# design.net
KiCad netlist of a schematic drawn in Altium Designer
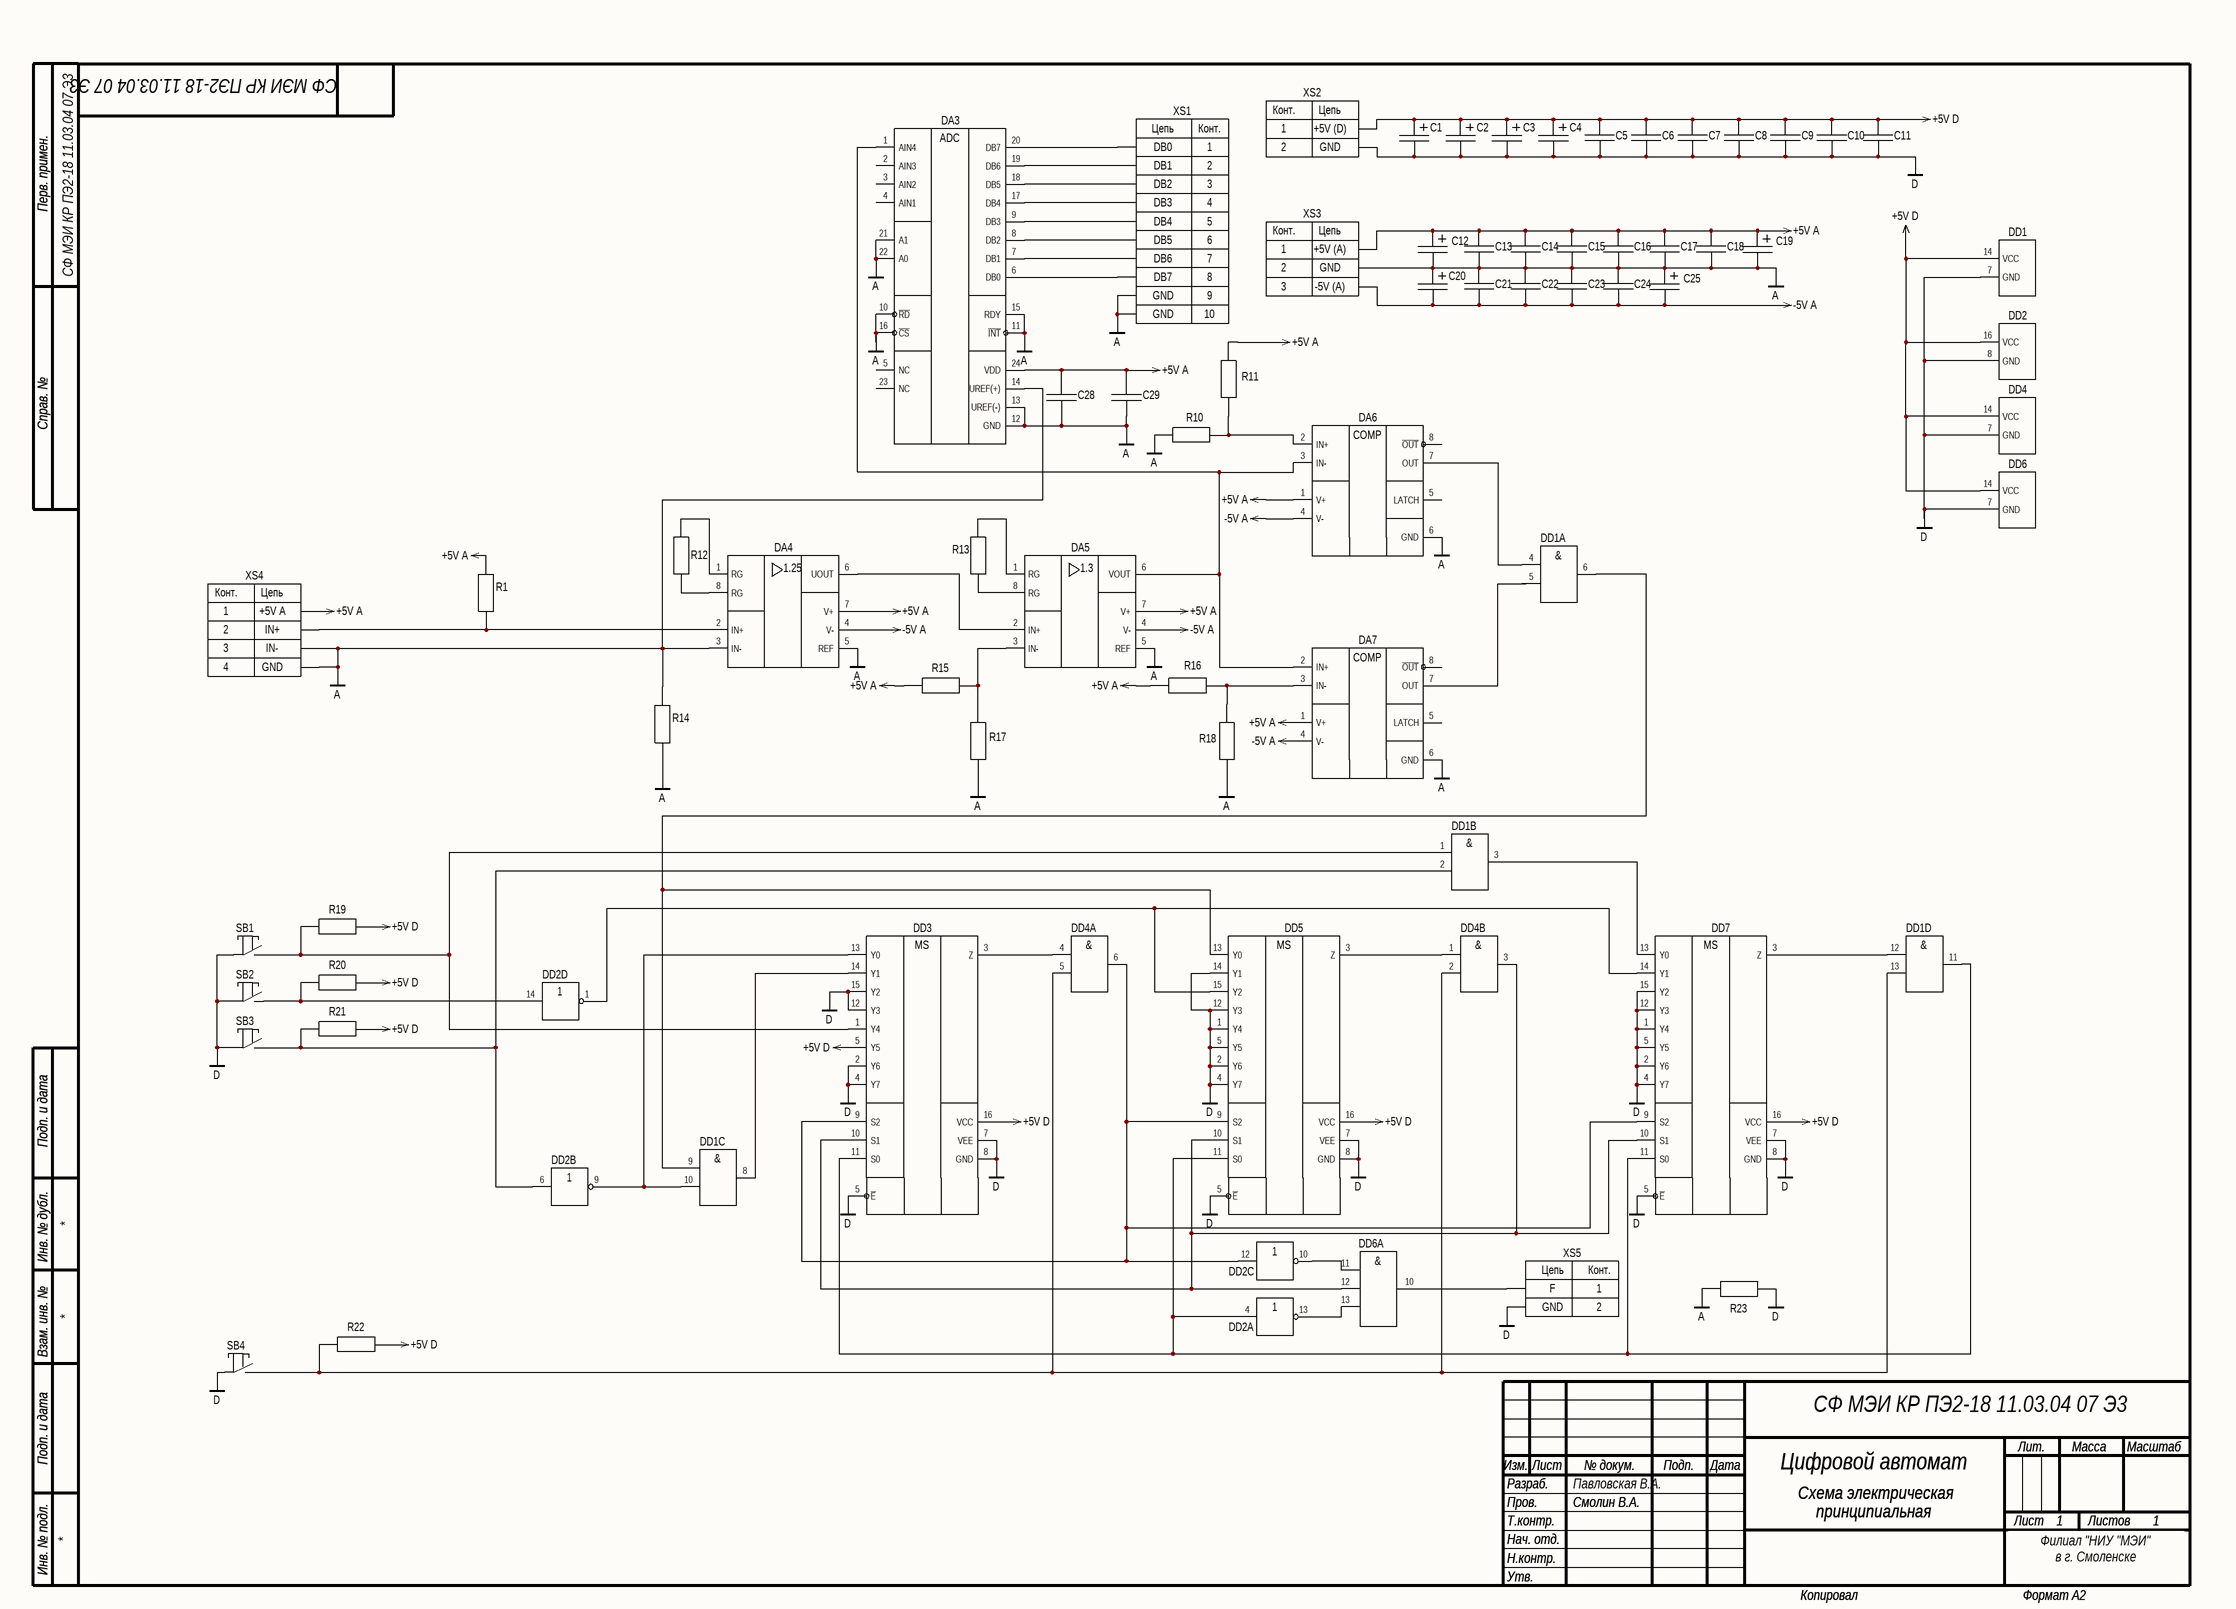
[diagram p0: Схема принципиальнаяСаня.SchDoc]

(export (version "E")
  (design (tool "Eeschema 10.0.6"))
  (components
    (comp (ref "C5")
      (value "0.1uF")
      (footprint "Кер.ЧИП конд. 0.1 мкФ X7R 50В 10% 0805")
      (description "Кер.ЧИП конд. 0.1 мкФ X7R 50В 10% 0805")
      (libsource (lib "УГО") (part "Кер.ЧИП конд. 0.1 мкФ X7R 50В 10% 0805"))
    )
    (comp (ref "C6")
      (value "0.1uF")
      (footprint "Кер.ЧИП конд. 0.1 мкФ X7R 50В 10% 0805")
      (description "Кер.ЧИП конд. 0.1 мкФ X7R 50В 10% 0805")
      (libsource (lib "УГО") (part "Кер.ЧИП конд. 0.1 мкФ X7R 50В 10% 0805"))
    )
    (comp (ref "C7")
      (value "0.1uF")
      (footprint "Кер.ЧИП конд. 0.1 мкФ X7R 50В 10% 0805")
      (description "Кер.ЧИП конд. 0.1 мкФ X7R 50В 10% 0805")
      (libsource (lib "УГО") (part "Кер.ЧИП конд. 0.1 мкФ X7R 50В 10% 0805"))
    )
    (comp (ref "C8")
      (value "0.1uF")
      (footprint "Кер.ЧИП конд. 0.1 мкФ X7R 50В 10% 0805")
      (description "Кер.ЧИП конд. 0.1 мкФ X7R 50В 10% 0805")
      (libsource (lib "УГО") (part "Кер.ЧИП конд. 0.1 мкФ X7R 50В 10% 0805"))
    )
    (comp (ref "C9")
      (value "0.1uF")
      (footprint "Кер.ЧИП конд. 0.1 мкФ X7R 50В 10% 0805")
      (description "Кер.ЧИП конд. 0.1 мкФ X7R 50В 10% 0805")
      (libsource (lib "УГО") (part "Кер.ЧИП конд. 0.1 мкФ X7R 50В 10% 0805"))
    )
    (comp (ref "C10")
      (value "0.1uF")
      (footprint "Кер.ЧИП конд. 0.1 мкФ X7R 50В 10% 0805")
      (description "Кер.ЧИП конд. 0.1 мкФ X7R 50В 10% 0805")
      (libsource (lib "УГО") (part "Кер.ЧИП конд. 0.1 мкФ X7R 50В 10% 0805"))
    )
    (comp (ref "C11")
      (value "0.1uF")
      (footprint "Кер.ЧИП конд. 0.1 мкФ X7R 50В 10% 0805")
      (description "Кер.ЧИП конд. 0.1 мкФ X7R 50В 10% 0805")
      (libsource (lib "УГО") (part "Кер.ЧИП конд. 0.1 мкФ X7R 50В 10% 0805"))
    )
    (comp (ref "C13")
      (value "0.1uF")
      (footprint "Кер.ЧИП конд. 0.1 мкФ X7R 50В 10% 0805")
      (description "Кер.ЧИП конд. 0.1 мкФ X7R 50В 10% 0805")
      (libsource (lib "УГО") (part "Кер.ЧИП конд. 0.1 мкФ X7R 50В 10% 0805"))
    )
    (comp (ref "C14")
      (value "0.1uF")
      (footprint "Кер.ЧИП конд. 0.1 мкФ X7R 50В 10% 0805")
      (description "Кер.ЧИП конд. 0.1 мкФ X7R 50В 10% 0805")
      (libsource (lib "УГО") (part "Кер.ЧИП конд. 0.1 мкФ X7R 50В 10% 0805"))
    )
    (comp (ref "C15")
      (value "0.1uF")
      (footprint "Кер.ЧИП конд. 0.1 мкФ X7R 50В 10% 0805")
      (description "Кер.ЧИП конд. 0.1 мкФ X7R 50В 10% 0805")
      (libsource (lib "УГО") (part "Кер.ЧИП конд. 0.1 мкФ X7R 50В 10% 0805"))
    )
    (comp (ref "C16")
      (value "0.1uF")
      (footprint "Кер.ЧИП конд. 0.1 мкФ X7R 50В 10% 0805")
      (description "Кер.ЧИП конд. 0.1 мкФ X7R 50В 10% 0805")
      (libsource (lib "УГО") (part "Кер.ЧИП конд. 0.1 мкФ X7R 50В 10% 0805"))
    )
    (comp (ref "C17")
      (value "0.1uF")
      (footprint "Кер.ЧИП конд. 0.1 мкФ X7R 50В 10% 0805")
      (description "Кер.ЧИП конд. 0.1 мкФ X7R 50В 10% 0805")
      (libsource (lib "УГО") (part "Кер.ЧИП конд. 0.1 мкФ X7R 50В 10% 0805"))
    )
    (comp (ref "C18")
      (value "0.1uF")
      (footprint "Кер.ЧИП конд. 0.1 мкФ X7R 50В 10% 0805")
      (description "Кер.ЧИП конд. 0.1 мкФ X7R 50В 10% 0805")
      (libsource (lib "УГО") (part "Кер.ЧИП конд. 0.1 мкФ X7R 50В 10% 0805"))
    )
    (comp (ref "C21")
      (value "0.1uF")
      (footprint "Кер.ЧИП конд. 0.1 мкФ X7R 50В 10% 0805")
      (description "Кер.ЧИП конд. 0.1 мкФ X7R 50В 10% 0805")
      (libsource (lib "УГО") (part "Кер.ЧИП конд. 0.1 мкФ X7R 50В 10% 0805"))
    )
    (comp (ref "C22")
      (value "0.1uF")
      (footprint "Кер.ЧИП конд. 0.1 мкФ X7R 50В 10% 0805")
      (description "Кер.ЧИП конд. 0.1 мкФ X7R 50В 10% 0805")
      (libsource (lib "УГО") (part "Кер.ЧИП конд. 0.1 мкФ X7R 50В 10% 0805"))
    )
    (comp (ref "C23")
      (value "0.1uF")
      (footprint "Кер.ЧИП конд. 0.1 мкФ X7R 50В 10% 0805")
      (description "Кер.ЧИП конд. 0.1 мкФ X7R 50В 10% 0805")
      (libsource (lib "УГО") (part "Кер.ЧИП конд. 0.1 мкФ X7R 50В 10% 0805"))
    )
    (comp (ref "C24")
      (value "0.1uF")
      (footprint "Кер.ЧИП конд. 0.1 мкФ X7R 50В 10% 0805")
      (description "Кер.ЧИП конд. 0.1 мкФ X7R 50В 10% 0805")
      (libsource (lib "УГО") (part "Кер.ЧИП конд. 0.1 мкФ X7R 50В 10% 0805"))
    )
    (comp (ref "C28")
      (value "0.1uF")
      (footprint "Кер.ЧИП конд. 0.1 мкФ X7R 50В 10% 0805")
      (description "Кер.ЧИП конд. 0.1 мкФ X7R 50В 10% 0805")
      (libsource (lib "УГО") (part "Кер.ЧИП конд. 0.1 мкФ X7R 50В 10% 0805"))
    )
    (comp (ref "C29")
      (value "47uF")
      (footprint "Кер.ЧИП конд. 47 мкФ X5R 20% 10В 1206")
      (description "Кер.ЧИП конд. 47 мкФ X5R 20% 10В 1206")
      (libsource (lib "УГО") (part "Кер.ЧИП конд. 47 мкФ X5R 20% 10В 1206"))
    )
    (comp (ref "DA4")
      (value "INA118E_BB")
      (footprint "AD620 Инструмент.усилитель")
      (libsource (lib "УГО") (part "INA118E_BB"))
    )
    (comp (ref "DA5")
      (value "INA118E_BB_1")
      (footprint "AD620 Инструмент.усилитель")
      (libsource (lib "УГО") (part "INA118E_BB_1"))
    )
    (comp (ref "DA6") (value "AD8561") (footprint "AD8561") (libsource (lib "УГО") (part "AD8561")))
    (comp (ref "DA7") (value "AD8561") (footprint "AD8561") (libsource (lib "УГО") (part "AD8561")))
    (comp (ref "DA33") (value "AD7824") (footprint "AD7824") (libsource (lib "УГО") (part "AD7824")))
    (comp (ref "DD1")
      (value "И №1 (4 компонента)")
      (footprint "4x2И")
      (libsource (lib "УГО") (part "И №1 (4 компонента)"))
    )
    (comp (ref "DD2")
      (value "НЕ №3 (4 компонента)")
      (footprint "CD4044B")
      (libsource (lib "УГО") (part "НЕ №3 (4 компонента)"))
    )
    (comp (ref "DD3")
      (value "Мультиплексор")
      (footprint "Мультиплексор")
      (description "74HC40510")
      (libsource (lib "УГО") (part "Мультиплексор"))
    )
    (comp (ref "DD4")
      (value "И №2 (2 компонента)")
      (footprint "4x2И")
      (libsource (lib "УГО") (part "И №2 (2 компонента)"))
    )
    (comp (ref "DD5")
      (value "Мультиплексор")
      (footprint "Мультиплексор")
      (description "74HC40510")
      (libsource (lib "УГО") (part "Мультиплексор"))
    )
    (comp (ref "DD6") (value "3И №1") (footprint "4x2И") (libsource (lib "УГО") (part "3И №1")))
    (comp (ref "DD7")
      (value "Мультиплексор")
      (footprint "Мультиплексор")
      (description "74HC40510")
      (libsource (lib "УГО") (part "Мультиплексор"))
    )
    (comp (ref "R1")
      (value "51k")
      (footprint "0.125Вт 0805 51 кОм, 5%, Чип резистор (SMD)")
      (description "0.125Вт 0805 51 кОм, 5%, Чип резистор (SMD)")
      (libsource (lib "УГО") (part "0.125Вт 0805 51 кОм, 5%, Чип резистор (SMD)"))
    )
    (comp (ref "R10")
      (value "1.5k")
      (footprint "0.125Вт 0805 15Ом, 5%, Чип резистор (SMD)")
      (description "0.125Вт 0805 15Ом, 5%, Чип резистор (SMD)")
      (libsource (lib "УГО") (part "0.125Вт 0805 15Ом, 5%, Чип резистор (SMD)_2_1"))
    )
    (comp (ref "R11")
      (value "8.2k")
      (footprint "0.125Вт 0805 82Ом, 5%, Чип резистор (SMD)")
      (description "0.125Вт 0805 82Ом, 5%, Чип резистор (SMD)")
      (libsource (lib "УГО") (part "0.125Вт 0805 82Ом, 5%, Чип резистор (SMD)_2_2"))
    )
    (comp (ref "R12")
      (value "200k")
      (footprint "0.125Вт 0805 200 кОм, 5%, Чип резистор (SMD)")
      (description "0.125Вт 0805 200 кОм, 5%, Чип резистор (SMD)")
      (libsource (lib "УГО") (part "0.125Вт 0805 200 кОм, 5%, Чип резистор (SMD)"))
    )
    (comp (ref "R13")
      (value "160k")
      (footprint "0.125Вт 0805 160 кОм, 5%, Чип резистор (SMD)")
      (description "0.125Вт 0805 160 кОм, 5%, Чип резистор (SMD)")
      (libsource (lib "УГО") (part "0.125Вт 0805 160 кОм, 5%, Чип резистор (SMD)"))
    )
    (comp (ref "R14")
      (value "51k")
      (footprint "0.125Вт 0805 51 кОм, 5%, Чип резистор (SMD)")
      (description "0.125Вт 0805 51 кОм, 5%, Чип резистор (SMD)")
      (libsource (lib "УГО") (part "0.125Вт 0805 51 кОм, 5%, Чип резистор (SMD)"))
    )
    (comp (ref "R15")
      (value "7.5k")
      (footprint "0.125Вт 0805 75Ом, 5%, Чип резистор (SMD)")
      (description "0.125Вт 0805 75Ом, 5%, Чип резистор (SMD)")
      (libsource (lib "УГО") (part "0.125Вт 0805 75Ом, 5%, Чип резистор (SMD)"))
    )
    (comp (ref "R16")
      (value "1k")
      (footprint "0.125Вт 0805 91Ом, 5%, Чип резистор (SMD)")
      (description "0.125Вт 0805 91Ом, 5%, Чип резистор (SMD)")
      (libsource (lib "УГО") (part "0.125Вт 0805 91кОм, 5%, Чип резистор (SMD)_1"))
    )
    (comp (ref "R17")
      (value "2.2k")
      (footprint "0.125Вт 0805 22Ом, 5%, Чип резистор (SMD)")
      (description "0.125Вт 0805 22Ом, 5%, Чип резистор (SMD)")
      (libsource (lib "УГО") (part "0.125Вт 0805 22Ом, 5%, Чип резистор (SMD)"))
    )
    (comp (ref "R18")
      (value "56")
      (footprint "0.125Вт 0805 5.1Ом, 5%, Чип резистор (SMD)")
      (description "0.125Вт 0805 5.1Ом, 5%, Чип резистор (SMD)")
      (libsource (lib "УГО") (part "0.125Вт 0805 5.1Ом, 5%, Чип резистор (SMD)_2"))
    )
    (comp (ref "R19")
      (value "10k")
      (footprint "0.125Вт 0805 3 кОм, 5%, Чип резистор (SMD)")
      (description "0.125Вт 0805 5кОм, 5%, Чип резистор (SMD)")
      (libsource (lib "УГО") (part "0.125Вт 0805 5кОм, 5%, Чип резистор (SMD)"))
    )
    (comp (ref "R20")
      (value "10k")
      (footprint "0.125Вт 0805 3 кОм, 5%, Чип резистор (SMD)")
      (description "0.125Вт 0805 5кОм, 5%, Чип резистор (SMD)")
      (libsource (lib "УГО") (part "0.125Вт 0805 5кОм, 5%, Чип резистор (SMD)"))
    )
    (comp (ref "R21")
      (value "10k")
      (footprint "0.125Вт 0805 3 кОм, 5%, Чип резистор (SMD)")
      (description "0.125Вт 0805 5кОм, 5%, Чип резистор (SMD)")
      (libsource (lib "УГО") (part "0.125Вт 0805 5кОм, 5%, Чип резистор (SMD)"))
    )
    (comp (ref "R22")
      (value "10k")
      (footprint "0.125Вт 0805 3 кОм, 5%, Чип резистор (SMD)")
      (description "0.125Вт 0805 5кОм, 5%, Чип резистор (SMD)")
      (libsource (lib "УГО") (part "0.125Вт 0805 5кОм, 5%, Чип резистор (SMD)"))
    )
    (comp (ref "R23")
      (value "0")
      (footprint "0.125Вт 0805 82Ом, 5%, Чип резистор (SMD)")
      (description "0.125Вт 0805 82Ом, 5%, Чип резистор (SMD)")
      (libsource (lib "УГО") (part "0.125Вт 0805 82Ом, 5%, Чип резистор (SMD)_2_2"))
    )
    (comp (ref "SB1")
      (value "Выключатель кнопочный с замыкающим контактом")
      (footprint "Выключатель кнопочный ese21x")
      (libsource (lib "УГО") (part "Выключатель кнопочный с замыкающим контактом"))
    )
    (comp (ref "SB2")
      (value "Выключатель кнопочный с замыкающим контактом")
      (footprint "Выключатель кнопочный ese21x")
      (libsource (lib "УГО") (part "Выключатель кнопочный с замыкающим контактом"))
    )
    (comp (ref "SB3")
      (value "Выключатель кнопочный с замыкающим контактом")
      (footprint "Выключатель кнопочный ese21x")
      (libsource (lib "УГО") (part "Выключатель кнопочный с замыкающим контактом"))
    )
    (comp (ref "SB4")
      (value "Выключатель кнопочный с замыкающим контактом")
      (footprint "Выключатель кнопочный ese21x")
      (libsource (lib "УГО") (part "Выключатель кнопочный с замыкающим контактом"))
    )
    (comp (ref "XS1") (value "XS 10Pin") (footprint "CI1108M1H") (libsource (lib "УГО") (part "XS 10Pin")))
    (comp (ref "XS2")
      (value "XS 2Pin (D)")
      (footprint "CI1102M1H  (F)")
      (libsource (lib "УГО") (part "XS 2Pin (D)"))
    )
    (comp (ref "XS3")
      (value "XS 3Pin (A)")
      (footprint "CI1108M1H - duplicate")
      (libsource (lib "УГО") (part "XS 3Pin (A)"))
    )
    (comp (ref "XS4") (value "XS Датчик") (footprint "CI1102M1H") (libsource (lib "УГО") (part "XS Датчик")))
    (comp (ref "XS5")
      (value "XS 2Pin_1")
      (footprint "CI1102M1H  (F)")
      (libsource (lib "УГО") (part "XS 2Pin_1"))
    )
    (comp (ref "С1")
      (value "1uF")
      (footprint "ECAP SMD, 1 мкФ, 50В, Конденсатор электролитический алюминиевый SMD")
      (description "ECAP SMD, 1 мкФ, 50В, Конденсатор электролитический алюминиевый SMD")
      (libsource (lib "УГО") (part "ECAP SMD, 1 мкФ, 50В, Конденсатор электролитический алюминиевый SMD"))
    )
    (comp (ref "С2")
      (value "1uF")
      (footprint "ECAP SMD, 1 мкФ, 50В, Конденсатор электролитический алюминиевый SMD")
      (description "ECAP SMD, 1 мкФ, 50В, Конденсатор электролитический алюминиевый SMD")
      (libsource (lib "УГО") (part "ECAP SMD, 1 мкФ, 50В, Конденсатор электролитический алюминиевый SMD"))
    )
    (comp (ref "С3")
      (value "1uF")
      (footprint "ECAP SMD, 1 мкФ, 50В, Конденсатор электролитический алюминиевый SMD")
      (description "ECAP SMD, 1 мкФ, 50В, Конденсатор электролитический алюминиевый SMD")
      (libsource (lib "УГО") (part "ECAP SMD, 1 мкФ, 50В, Конденсатор электролитический алюминиевый SMD"))
    )
    (comp (ref "С4")
      (value "1uF")
      (footprint "ECAP SMD, 1 мкФ, 50В, Конденсатор электролитический алюминиевый SMD")
      (description "ECAP SMD, 1 мкФ, 50В, Конденсатор электролитический алюминиевый SMD")
      (libsource (lib "УГО") (part "ECAP SMD, 1 мкФ, 50В, Конденсатор электролитический алюминиевый SMD"))
    )
    (comp (ref "С12")
      (value "1uF")
      (footprint "ECAP SMD, 1 мкФ, 50В, Конденсатор электролитический алюминиевый SMD")
      (description "ECAP SMD, 1 мкФ, 50В, Конденсатор электролитический алюминиевый SMD")
      (libsource (lib "УГО") (part "ECAP SMD, 1 мкФ, 50В, Конденсатор электролитический алюминиевый SMD"))
    )
    (comp (ref "С19")
      (value "1uF")
      (footprint "ECAP SMD, 1 мкФ, 50В, Конденсатор электролитический алюминиевый SMD")
      (description "ECAP SMD, 1 мкФ, 50В, Конденсатор электролитический алюминиевый SMD")
      (libsource (lib "УГО") (part "ECAP SMD, 1 мкФ, 50В, Конденсатор электролитический алюминиевый SMD"))
    )
    (comp (ref "С20")
      (value "1uF")
      (footprint "ECAP SMD, 1 мкФ, 50В, Конденсатор электролитический алюминиевый SMD")
      (description "ECAP SMD, 1 мкФ, 50В, Конденсатор электролитический алюминиевый SMD")
      (libsource (lib "УГО") (part "ECAP SMD, 1 мкФ, 50В, Конденсатор электролитический алюминиевый SMD"))
    )
    (comp (ref "С25")
      (value "1uF")
      (footprint "ECAP SMD, 1 мкФ, 50В, Конденсатор электролитический алюминиевый SMD")
      (description "ECAP SMD, 1 мкФ, 50В, Конденсатор электролитический алюминиевый SMD")
      (libsource (lib "УГО") (part "ECAP SMD, 1 мкФ, 50В, Конденсатор электролитический алюминиевый SMD"))
    )
  )
  (nets
    (net (code "1") (name "+5V A") (class "Default")
      (node (ref "C13") (pin "2") (pinfunction "2_2") (pintype "passive"))
      (node (ref "C14") (pin "2") (pinfunction "2_2") (pintype "passive"))
      (node (ref "C15") (pin "2") (pinfunction "2_2") (pintype "passive"))
      (node (ref "C16") (pin "2") (pinfunction "2_2") (pintype "passive"))
      (node (ref "C17") (pin "2") (pinfunction "2_2") (pintype "passive"))
      (node (ref "C18") (pin "2") (pinfunction "2_2") (pintype "passive"))
      (node (ref "C28") (pin "2") (pinfunction "2_2") (pintype "passive"))
      (node (ref "C29") (pin "2") (pinfunction "2_2") (pintype "passive"))
      (node (ref "DA33") (pin "24") (pinfunction "VDD_24") (pintype "passive"))
      (node (ref "DA4") (pin "7") (pinfunction "V+_7") (pintype "passive"))
      (node (ref "DA5") (pin "7") (pinfunction "V+_7") (pintype "passive"))
      (node (ref "DA6") (pin "1") (pinfunction "V+_1") (pintype "passive"))
      (node (ref "DA7") (pin "1") (pinfunction "V+_1") (pintype "passive"))
      (node (ref "R1") (pin "1") (pinfunction "1_1") (pintype "passive"))
      (node (ref "R11") (pin "2") (pinfunction "2_2") (pintype "passive"))
      (node (ref "R15") (pin "1") (pinfunction "1_1") (pintype "passive"))
      (node (ref "R16") (pin "1") (pinfunction "1_1") (pintype "passive"))
      (node (ref "XS3") (pin "1") (pinfunction "Pin1_1") (pintype "passive"))
      (node (ref "XS4") (pin "1") (pinfunction "Pin1_1") (pintype "passive"))
      (node (ref "С12") (pin "1") (pinfunction "1_1") (pintype "passive"))
      (node (ref "С19") (pin "1") (pinfunction "1_1") (pintype "passive"))
    )
    (net (code "2") (name "+5V D") (class "Default")
      (node (ref "C10") (pin "2") (pinfunction "2_2") (pintype "passive"))
      (node (ref "C11") (pin "2") (pinfunction "2_2") (pintype "passive"))
      (node (ref "C5") (pin "2") (pinfunction "2_2") (pintype "passive"))
      (node (ref "C6") (pin "2") (pinfunction "2_2") (pintype "passive"))
      (node (ref "C7") (pin "2") (pinfunction "2_2") (pintype "passive"))
      (node (ref "C8") (pin "2") (pinfunction "2_2") (pintype "passive"))
      (node (ref "C9") (pin "2") (pinfunction "2_2") (pintype "passive"))
      (node (ref "DD1") (pin "14") (pinfunction "VCC_14") (pintype "passive"))
      (node (ref "DD2") (pin "16") (pinfunction "VCC_16") (pintype "passive"))
      (node (ref "DD3") (pin "16") (pinfunction "VCC_16") (pintype "passive"))
      (node (ref "DD3") (pin "5") (pinfunction "Y5_5") (pintype "passive"))
      (node (ref "DD4") (pin "14") (pinfunction "VCC_14") (pintype "passive"))
      (node (ref "DD5") (pin "16") (pinfunction "VCC_16") (pintype "passive"))
      (node (ref "DD6") (pin "14") (pinfunction "VCC_14") (pintype "passive"))
      (node (ref "DD7") (pin "16") (pinfunction "VCC_16") (pintype "passive"))
      (node (ref "R19") (pin "2") (pinfunction "2_2") (pintype "passive"))
      (node (ref "R20") (pin "2") (pinfunction "2_2") (pintype "passive"))
      (node (ref "R21") (pin "2") (pinfunction "2_2") (pintype "passive"))
      (node (ref "R22") (pin "2") (pinfunction "2_2") (pintype "passive"))
      (node (ref "XS2") (pin "1") (pinfunction "Pin1_1") (pintype "passive"))
      (node (ref "С1") (pin "1") (pinfunction "1_1") (pintype "passive"))
      (node (ref "С2") (pin "1") (pinfunction "1_1") (pintype "passive"))
      (node (ref "С3") (pin "1") (pinfunction "1_1") (pintype "passive"))
      (node (ref "С4") (pin "1") (pinfunction "1_1") (pintype "passive"))
    )
    (net (code "3") (name "-5V A") (class "Default")
      (node (ref "C21") (pin "1") (pinfunction "1_1") (pintype "passive"))
      (node (ref "C22") (pin "1") (pinfunction "1_1") (pintype "passive"))
      (node (ref "C23") (pin "1") (pinfunction "1_1") (pintype "passive"))
      (node (ref "C24") (pin "1") (pinfunction "1_1") (pintype "passive"))
      (node (ref "DA4") (pin "4") (pinfunction "V-_4") (pintype "passive"))
      (node (ref "DA5") (pin "4") (pinfunction "V-_4") (pintype "passive"))
      (node (ref "DA6") (pin "4") (pinfunction "V-_4") (pintype "passive"))
      (node (ref "DA7") (pin "4") (pinfunction "V-_4") (pintype "passive"))
      (node (ref "XS3") (pin "3") (pinfunction "Pin3_3") (pintype "passive"))
      (node (ref "С20") (pin "2") (pinfunction "2_2") (pintype "passive"))
      (node (ref "С25") (pin "2") (pinfunction "2_2") (pintype "passive"))
    )
    (net (code "4") (name "A") (class "Default")
      (node (ref "C13") (pin "1") (pinfunction "1_1") (pintype "passive"))
      (node (ref "C14") (pin "1") (pinfunction "1_1") (pintype "passive"))
      (node (ref "C15") (pin "1") (pinfunction "1_1") (pintype "passive"))
      (node (ref "C16") (pin "1") (pinfunction "1_1") (pintype "passive"))
      (node (ref "C17") (pin "1") (pinfunction "1_1") (pintype "passive"))
      (node (ref "C18") (pin "1") (pinfunction "1_1") (pintype "passive"))
      (node (ref "C21") (pin "2") (pinfunction "2_2") (pintype "passive"))
      (node (ref "C22") (pin "2") (pinfunction "2_2") (pintype "passive"))
      (node (ref "C23") (pin "2") (pinfunction "2_2") (pintype "passive"))
      (node (ref "C24") (pin "2") (pinfunction "2_2") (pintype "passive"))
      (node (ref "C28") (pin "1") (pinfunction "1_1") (pintype "passive"))
      (node (ref "C29") (pin "1") (pinfunction "1_1") (pintype "passive"))
      (node (ref "DA33") (pin "10") (pinfunction "~{RD}_10") (pintype "passive"))
      (node (ref "DA33") (pin "11") (pinfunction "~{INT}_11") (pintype "passive"))
      (node (ref "DA33") (pin "12") (pinfunction "GND_12") (pintype "passive"))
      (node (ref "DA33") (pin "13") (pinfunction "UREF(-)_13") (pintype "passive"))
      (node (ref "DA33") (pin "14") (pinfunction "UREF(+)_14") (pintype "passive"))
      (node (ref "DA33") (pin "15") (pinfunction "RDY_15") (pintype "passive"))
      (node (ref "DA33") (pin "16") (pinfunction "~{CS}_16") (pintype "passive"))
      (node (ref "DA33") (pin "21") (pinfunction "A1_21") (pintype "passive"))
      (node (ref "DA33") (pin "22") (pinfunction "A0_22") (pintype "passive"))
      (node (ref "DA4") (pin "3") (pinfunction "IN-_3") (pintype "passive"))
      (node (ref "DA4") (pin "5") (pinfunction "REF_5") (pintype "passive"))
      (node (ref "DA5") (pin "5") (pinfunction "REF_5") (pintype "passive"))
      (node (ref "DA6") (pin "6") (pinfunction "GND_6") (pintype "passive"))
      (node (ref "DA7") (pin "6") (pinfunction "GND_6") (pintype "passive"))
      (node (ref "R10") (pin "1") (pinfunction "1_1") (pintype "passive"))
      (node (ref "R14") (pin "1") (pinfunction "1_1") (pintype "passive"))
      (node (ref "R14") (pin "2") (pinfunction "2_2") (pintype "passive"))
      (node (ref "R17") (pin "1") (pinfunction "1_1") (pintype "passive"))
      (node (ref "R18") (pin "1") (pinfunction "1_1") (pintype "passive"))
      (node (ref "R23") (pin "2") (pinfunction "2_2") (pintype "passive"))
      (node (ref "XS1") (pin "10") (pinfunction "Pin10_10") (pintype "passive"))
      (node (ref "XS1") (pin "9") (pinfunction "Pin9_9") (pintype "passive"))
      (node (ref "XS3") (pin "2") (pinfunction "Pin2_2") (pintype "passive"))
      (node (ref "XS4") (pin "3") (pinfunction "3_3") (pintype "passive"))
      (node (ref "XS4") (pin "4") (pinfunction "4_4") (pintype "passive"))
      (node (ref "С12") (pin "2") (pinfunction "2_2") (pintype "passive"))
      (node (ref "С19") (pin "2") (pinfunction "2_2") (pintype "passive"))
      (node (ref "С20") (pin "1") (pinfunction "1_1") (pintype "passive"))
      (node (ref "С25") (pin "1") (pinfunction "1_1") (pintype "passive"))
    )
    (net (code "5") (name "D") (class "Default")
      (node (ref "C10") (pin "1") (pinfunction "1_1") (pintype "passive"))
      (node (ref "C11") (pin "1") (pinfunction "1_1") (pintype "passive"))
      (node (ref "C5") (pin "1") (pinfunction "1_1") (pintype "passive"))
      (node (ref "C6") (pin "1") (pinfunction "1_1") (pintype "passive"))
      (node (ref "C7") (pin "1") (pinfunction "1_1") (pintype "passive"))
      (node (ref "C8") (pin "1") (pinfunction "1_1") (pintype "passive"))
      (node (ref "C9") (pin "1") (pinfunction "1_1") (pintype "passive"))
      (node (ref "DD1") (pin "7") (pinfunction "GND_7") (pintype "passive"))
      (node (ref "DD2") (pin "8") (pinfunction "GND_8") (pintype "passive"))
      (node (ref "DD3") (pin "12") (pinfunction "Y3_12") (pintype "passive"))
      (node (ref "DD3") (pin "15") (pinfunction "Y2_15") (pintype "passive"))
      (node (ref "DD3") (pin "2") (pinfunction "Y6_2") (pintype "passive"))
      (node (ref "DD3") (pin "4") (pinfunction "Y7_4") (pintype "passive"))
      (node (ref "DD3") (pin "5") (pinfunction "~{E}_5") (pintype "passive"))
      (node (ref "DD3") (pin "7") (pinfunction "VEE_7") (pintype "passive"))
      (node (ref "DD3") (pin "8") (pinfunction "GND_8") (pintype "passive"))
      (node (ref "DD4") (pin "7") (pinfunction "GND_7") (pintype "passive"))
      (node (ref "DD5") (pin "1") (pinfunction "Y4_1") (pintype "passive"))
      (node (ref "DD5") (pin "12") (pinfunction "Y3_12") (pintype "passive"))
      (node (ref "DD5") (pin "14") (pinfunction "Y1_14") (pintype "passive"))
      (node (ref "DD5") (pin "2") (pinfunction "Y6_2") (pintype "passive"))
      (node (ref "DD5") (pin "4") (pinfunction "Y7_4") (pintype "passive"))
      (node (ref "DD5") (pin "5") (pinfunction "~{E}_5") (pintype "passive"))
      (node (ref "DD5") (pin "7") (pinfunction "VEE_7") (pintype "passive"))
      (node (ref "DD5") (pin "8") (pinfunction "GND_8") (pintype "passive"))
      (node (ref "DD6") (pin "7") (pinfunction "GND_7") (pintype "passive"))
      (node (ref "DD7") (pin "1") (pinfunction "Y4_1") (pintype "passive"))
      (node (ref "DD7") (pin "12") (pinfunction "Y3_12") (pintype "passive"))
      (node (ref "DD7") (pin "15") (pinfunction "Y2_15") (pintype "passive"))
      (node (ref "DD7") (pin "2") (pinfunction "Y6_2") (pintype "passive"))
      (node (ref "DD7") (pin "4") (pinfunction "Y7_4") (pintype "passive"))
      (node (ref "DD7") (pin "5") (pinfunction "Y5_5") (pintype "passive"))
      (node (ref "DD7") (pin "7") (pinfunction "VEE_7") (pintype "passive"))
      (node (ref "DD7") (pin "8") (pinfunction "GND_8") (pintype "passive"))
      (node (ref "R23") (pin "1") (pinfunction "1_1") (pintype "passive"))
      (node (ref "SB1") (pin "1") (pintype "passive"))
      (node (ref "SB2") (pin "1") (pintype "passive"))
      (node (ref "SB3") (pin "1") (pintype "passive"))
      (node (ref "SB4") (pin "1") (pintype "passive"))
      (node (ref "XS2") (pin "2") (pinfunction "Pin2_2") (pintype "passive"))
      (node (ref "XS5") (pin "2") (pinfunction "Pin2_2") (pintype "passive"))
      (node (ref "С1") (pin "2") (pinfunction "2_2") (pintype "passive"))
      (node (ref "С2") (pin "2") (pinfunction "2_2") (pintype "passive"))
      (node (ref "С3") (pin "2") (pinfunction "2_2") (pintype "passive"))
      (node (ref "С4") (pin "2") (pinfunction "2_2") (pintype "passive"))
    )
    (net (code "6") (name "Net-(DA4-IN+)") (class "Default")
      (node (ref "DA4") (pin "2") (pinfunction "IN+_2") (pintype "passive"))
      (node (ref "R1") (pin "2") (pinfunction "2_2") (pintype "passive"))
      (node (ref "XS4") (pin "2") (pinfunction "Pin2_2") (pintype "passive"))
    )
    (net (code "7") (name "Net-(DA4-RG-Pad1)") (class "Default")
      (node (ref "DA4") (pin "1") (pinfunction "RG_1") (pintype "passive"))
      (node (ref "R12") (pin "2") (pinfunction "2_2") (pintype "passive"))
    )
    (net (code "8") (name "Net-(DA4-RG-Pad8)") (class "Default")
      (node (ref "DA4") (pin "8") (pinfunction "RG_8") (pintype "passive"))
      (node (ref "R12") (pin "1") (pinfunction "1_1") (pintype "passive"))
    )
    (net (code "9") (name "Net-(DA4-UOUT)") (class "Default")
      (node (ref "DA4") (pin "6") (pinfunction "UOUT_6") (pintype "passive"))
      (node (ref "DA5") (pin "2") (pinfunction "IN+_2") (pintype "passive"))
    )
    (net (code "10") (name "Net-(DA5-IN-)") (class "Default")
      (node (ref "DA5") (pin "3") (pinfunction "IN-_3") (pintype "passive"))
      (node (ref "R15") (pin "2") (pinfunction "2_2") (pintype "passive"))
      (node (ref "R17") (pin "2") (pinfunction "2_2") (pintype "passive"))
    )
    (net (code "11") (name "Net-(DA5-RG-Pad1)") (class "Default")
      (node (ref "DA5") (pin "1") (pinfunction "RG_1") (pintype "passive"))
      (node (ref "R13") (pin "2") (pinfunction "2_2") (pintype "passive"))
    )
    (net (code "12") (name "Net-(DA5-RG-Pad8)") (class "Default")
      (node (ref "DA5") (pin "8") (pinfunction "RG_8") (pintype "passive"))
      (node (ref "R13") (pin "1") (pinfunction "1_1") (pintype "passive"))
    )
    (net (code "13") (name "Net-(DA6-IN+)") (class "Default")
      (node (ref "DA6") (pin "2") (pinfunction "IN+_2") (pintype "passive"))
      (node (ref "R10") (pin "2") (pinfunction "2_2") (pintype "passive"))
      (node (ref "R11") (pin "1") (pinfunction "1_1") (pintype "passive"))
    )
    (net (code "14") (name "Net-(DA6-OUT)") (class "Default")
      (node (ref "DA6") (pin "7") (pinfunction "OUT_7") (pintype "passive"))
      (node (ref "DD1") (pin "4") (pintype "passive"))
    )
    (net (code "15") (name "Net-(DA7-IN-)") (class "Default")
      (node (ref "DA7") (pin "3") (pinfunction "IN-_3") (pintype "passive"))
      (node (ref "R16") (pin "2") (pinfunction "2_2") (pintype "passive"))
      (node (ref "R18") (pin "2") (pinfunction "2_2") (pintype "passive"))
    )
    (net (code "16") (name "Net-(DA7-OUT)") (class "Default")
      (node (ref "DA7") (pin "7") (pinfunction "OUT_7") (pintype "passive"))
      (node (ref "DD1") (pin "5") (pintype "passive"))
    )
    (net (code "17") (name "Net-(DA33-AIN4)") (class "Default")
      (node (ref "DA33") (pin "1") (pinfunction "AIN4_1") (pintype "passive"))
      (node (ref "DA5") (pin "6") (pinfunction "VOUT_6") (pintype "passive"))
      (node (ref "DA6") (pin "3") (pinfunction "IN-_3") (pintype "passive"))
      (node (ref "DA7") (pin "2") (pinfunction "IN+_2") (pintype "passive"))
    )
    (net (code "18") (name "Net-(DA33-DB0)") (class "Default")
      (node (ref "DA33") (pin "6") (pinfunction "DB0_6") (pintype "passive"))
      (node (ref "XS1") (pin "8") (pinfunction "Pin8_8") (pintype "passive"))
    )
    (net (code "19") (name "Net-(DA33-DB1)") (class "Default")
      (node (ref "DA33") (pin "7") (pinfunction "DB1_7") (pintype "passive"))
      (node (ref "XS1") (pin "7") (pinfunction "Pin7_7") (pintype "passive"))
    )
    (net (code "20") (name "Net-(DA33-DB2)") (class "Default")
      (node (ref "DA33") (pin "8") (pinfunction "DB2_8") (pintype "passive"))
      (node (ref "XS1") (pin "6") (pinfunction "Pin6_6") (pintype "passive"))
    )
    (net (code "21") (name "Net-(DA33-DB3)") (class "Default")
      (node (ref "DA33") (pin "9") (pinfunction "DB3_9") (pintype "passive"))
      (node (ref "XS1") (pin "5") (pinfunction "Pin5_5") (pintype "passive"))
    )
    (net (code "22") (name "Net-(DA33-DB4)") (class "Default")
      (node (ref "DA33") (pin "17") (pinfunction "DB4_17") (pintype "passive"))
      (node (ref "XS1") (pin "4") (pinfunction "Pin4_4") (pintype "passive"))
    )
    (net (code "23") (name "Net-(DA33-DB5)") (class "Default")
      (node (ref "DA33") (pin "18") (pinfunction "DB5_18") (pintype "passive"))
      (node (ref "XS1") (pin "3") (pinfunction "Pin3_3") (pintype "passive"))
    )
    (net (code "24") (name "Net-(DA33-DB6)") (class "Default")
      (node (ref "DA33") (pin "19") (pinfunction "DB6_19") (pintype "passive"))
      (node (ref "XS1") (pin "2") (pinfunction "Pin2_2") (pintype "passive"))
    )
    (net (code "25") (name "Net-(DA33-DB7)") (class "Default")
      (node (ref "DA33") (pin "20") (pinfunction "DB7_20") (pintype "passive"))
      (node (ref "XS1") (pin "1") (pinfunction "Pin1_1") (pintype "passive"))
    )
    (net (code "26") (name "Net-(DD1-Pad2)") (class "Default")
      (node (ref "DD1") (pin "2") (pintype "passive"))
      (node (ref "DD2") (pin "6") (pintype "passive"))
      (node (ref "R21") (pin "1") (pinfunction "1_1") (pintype "passive"))
      (node (ref "SB3") (pin "2") (pintype "passive"))
    )
    (net (code "27") (name "Net-(DD1-Pad13)") (class "Default")
      (node (ref "DD1") (pin "13") (pintype "passive"))
      (node (ref "DD4") (pin "2") (pintype "passive"))
      (node (ref "DD4") (pin "5") (pintype "passive"))
      (node (ref "R22") (pin "1") (pinfunction "1_1") (pintype "passive"))
      (node (ref "SB4") (pin "2") (pintype "passive"))
    )
    (net (code "28") (name "Net-(DD2-Pad10)") (class "Default")
      (node (ref "DD2") (pin "10") (pintype "passive"))
      (node (ref "DD6") (pin "11") (pintype "passive"))
    )
    (net (code "29") (name "Net-(DD2-Pad13)") (class "Default")
      (node (ref "DD2") (pin "13") (pintype "passive"))
      (node (ref "DD6") (pin "13") (pintype "passive"))
    )
    (net (code "30") (name "Net-(DD2-Pad14)") (class "Default")
      (node (ref "DD2") (pin "14") (pintype "passive"))
      (node (ref "R20") (pin "1") (pinfunction "1_1") (pintype "passive"))
      (node (ref "SB2") (pin "2") (pintype "passive"))
    )
    (net (code "31") (name "Net-(DD3-S0)") (class "Default")
      (node (ref "DD1") (pin "11") (pintype "passive"))
      (node (ref "DD2") (pin "4") (pintype "passive"))
      (node (ref "DD3") (pin "11") (pinfunction "S0_11") (pintype "passive"))
      (node (ref "DD5") (pin "11") (pinfunction "S0_11") (pintype "passive"))
      (node (ref "DD7") (pin "11") (pinfunction "S0_11") (pintype "passive"))
    )
    (net (code "32") (name "Net-(DD3-S1)") (class "Default")
      (node (ref "DD3") (pin "10") (pinfunction "S1_10") (pintype "passive"))
      (node (ref "DD4") (pin "3") (pintype "passive"))
      (node (ref "DD5") (pin "10") (pinfunction "S1_10") (pintype "passive"))
      (node (ref "DD6") (pin "12") (pintype "passive"))
      (node (ref "DD7") (pin "10") (pinfunction "S1_10") (pintype "passive"))
    )
    (net (code "33") (name "Net-(DD3-S2)") (class "Default")
      (node (ref "DD2") (pin "12") (pintype "passive"))
      (node (ref "DD3") (pin "9") (pinfunction "S2_9") (pintype "passive"))
      (node (ref "DD4") (pin "6") (pintype "passive"))
      (node (ref "DD5") (pin "9") (pinfunction "S2_9") (pintype "passive"))
      (node (ref "DD7") (pin "9") (pinfunction "S2_9") (pintype "passive"))
    )
    (net (code "34") (name "Net-(DD3-Y0)") (class "Default")
      (node (ref "DD1") (pin "10") (pintype "passive"))
      (node (ref "DD2") (pin "9") (pintype "passive"))
      (node (ref "DD3") (pin "13") (pinfunction "Y0_13") (pintype "passive"))
    )
    (net (code "35") (name "Net-(DD3-Y1)") (class "Default")
      (node (ref "DD1") (pin "8") (pintype "passive"))
      (node (ref "DD3") (pin "14") (pinfunction "Y1_14") (pintype "passive"))
    )
    (net (code "36") (name "Net-(DD3-Y4)") (class "Default")
      (node (ref "DD1") (pin "1") (pintype "passive"))
      (node (ref "DD3") (pin "1") (pinfunction "Y4_1") (pintype "passive"))
      (node (ref "R19") (pin "1") (pinfunction "1_1") (pintype "passive"))
      (node (ref "SB1") (pin "2") (pintype "passive"))
    )
    (net (code "37") (name "Net-(DD3-Z)") (class "Default")
      (node (ref "DD3") (pin "3") (pinfunction "Z_3") (pintype "passive"))
      (node (ref "DD4") (pin "4") (pintype "passive"))
    )
    (net (code "38") (name "Net-(DD5-Y0)") (class "Default")
      (node (ref "DD1") (pin "6") (pintype "passive"))
      (node (ref "DD1") (pin "9") (pintype "passive"))
      (node (ref "DD5") (pin "13") (pinfunction "Y0_13") (pintype "passive"))
    )
    (net (code "39") (name "Net-(DD5-Y2)") (class "Default")
      (node (ref "DD2") (pin "1") (pintype "passive"))
      (node (ref "DD5") (pin "15") (pinfunction "Y2_15") (pintype "passive"))
      (node (ref "DD7") (pin "14") (pinfunction "Y1_14") (pintype "passive"))
    )
    (net (code "40") (name "Net-(DD5-Z)") (class "Default")
      (node (ref "DD4") (pin "1") (pintype "passive"))
      (node (ref "DD5") (pin "3") (pinfunction "Z_3") (pintype "passive"))
    )
    (net (code "41") (name "Net-(DD7-Y0)") (class "Default")
      (node (ref "DD1") (pin "3") (pintype "passive"))
      (node (ref "DD7") (pin "13") (pinfunction "Y0_13") (pintype "passive"))
    )
    (net (code "42") (name "Net-(DD7-Z)") (class "Default")
      (node (ref "DD1") (pin "12") (pintype "passive"))
      (node (ref "DD7") (pin "3") (pinfunction "Z_3") (pintype "passive"))
    )
    (net (code "43") (name "Net-(XS5-Pin1)") (class "Default")
      (node (ref "DD6") (pin "10") (pintype "passive"))
      (node (ref "XS5") (pin "1") (pinfunction "Pin1_1") (pintype "passive"))
    )
    (net (code "44") (name "unconnected-(DA6-LATCH-Pad5)") (class "Default")
      (node (ref "DA6") (pin "5") (pinfunction "LATCH_5") (pintype "passive"))
    )
    (net (code "45") (name "unconnected-(DA6-~{OUT}-Pad8)") (class "Default")
      (node (ref "DA6") (pin "8") (pinfunction "~{OUT}_8") (pintype "passive"))
    )
    (net (code "46") (name "unconnected-(DA7-LATCH-Pad5)") (class "Default")
      (node (ref "DA7") (pin "5") (pinfunction "LATCH_5") (pintype "passive"))
    )
    (net (code "47") (name "unconnected-(DA7-~{OUT}-Pad8)") (class "Default")
      (node (ref "DA7") (pin "8") (pinfunction "~{OUT}_8") (pintype "passive"))
    )
    (net (code "48") (name "unconnected-(DA33-AIN1-Pad4)") (class "Default")
      (node (ref "DA33") (pin "4") (pinfunction "AIN1_4") (pintype "passive"))
    )
    (net (code "49") (name "unconnected-(DA33-AIN2-Pad3)") (class "Default")
      (node (ref "DA33") (pin "3") (pinfunction "AIN2_3") (pintype "passive"))
    )
    (net (code "50") (name "unconnected-(DA33-AIN3-Pad2)") (class "Default")
      (node (ref "DA33") (pin "2") (pinfunction "AIN3_2") (pintype "passive"))
    )
    (net (code "51") (name "unconnected-(DA33-NC-Pad5)") (class "Default")
      (node (ref "DA33") (pin "5") (pinfunction "NC_5") (pintype "passive"))
    )
    (net (code "52") (name "unconnected-(DA33-NC-Pad23)") (class "Default")
      (node (ref "DA33") (pin "23") (pinfunction "NC_23") (pintype "passive"))
    )
  )
)
